# w10dc_motor.net
KiCad netlist of a schematic drawn in EAGLE
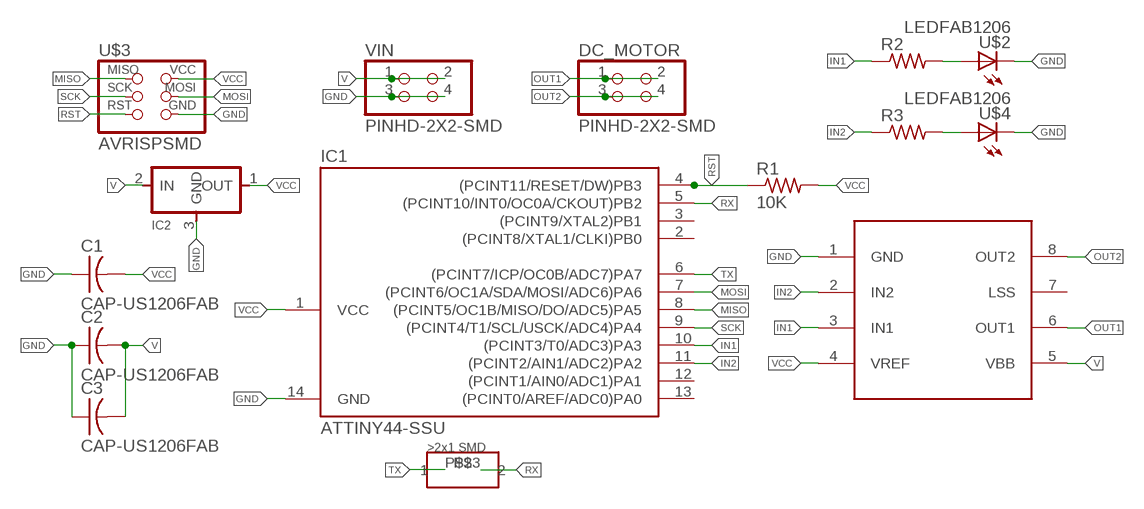
[diagram p0: schematic, sheet 1]

(export (version "E")
  (design (tool "Eeschema 10.0.6"))
  (components
    (comp (ref "C1")
      (value "CAP-US1206FAB")
      (footprint "eagle-import:C1206FAB")
      (libsource (lib "eagle-import") (part "CAP-US1206FAB"))
    )
    (comp (ref "C2")
      (value "CAP-US1206FAB")
      (footprint "eagle-import:C1206FAB")
      (libsource (lib "eagle-import") (part "CAP-US1206FAB"))
    )
    (comp (ref "C3")
      (value "CAP-US1206FAB")
      (footprint "eagle-import:C1206FAB")
      (libsource (lib "eagle-import") (part "CAP-US1206FAB"))
    )
    (comp (ref "DC_MOTOR")
      (value "PINHD-2X2-SMD")
      (footprint "eagle-import:2X02SMD")
      (libsource (lib "eagle-import") (part "PINHD-2X2-SMD"))
    )
    (comp (ref "IC1")
      (value "ATTINY44-SSU")
      (footprint "eagle-import:SOIC14")
      (libsource (lib "eagle-import") (part "ATTINY44-SSU"))
    )
    (comp (ref "IC2")
      (value "REGULATORSOT23")
      (footprint "eagle-import:SOT23")
      (libsource (lib "eagle-import") (part "REGULATORSOT23"))
    )
    (comp (ref "R1")
      (value "10K")
      (footprint "eagle-import:R1206FAB")
      (libsource (lib "eagle-import") (part "RES-US1206FAB"))
    )
    (comp (ref "R2")
      (value "RES-US1206FAB")
      (footprint "eagle-import:R1206FAB")
      (libsource (lib "eagle-import") (part "RES-US1206FAB"))
    )
    (comp (ref "R3")
      (value "RES-US1206FAB")
      (footprint "eagle-import:R1206FAB")
      (libsource (lib "eagle-import") (part "RES-US1206FAB"))
    )
    (comp (ref "U$1")
      (value "A4953-H-BRIDGE-MOTOR-DRIVER")
      (footprint "eagle-import:SOIC8")
      (libsource (lib "eagle-import") (part "A4953-H-BRIDGE-MOTOR-DRIVER"))
    )
    (comp (ref "U$2")
      (value "LEDFAB1206")
      (footprint "eagle-import:LED1206FAB")
      (libsource (lib "eagle-import") (part "LEDFAB1206"))
    )
    (comp (ref "U$3")
      (value "AVRISPSMD")
      (footprint "eagle-import:2X03SMD")
      (libsource (lib "eagle-import") (part "AVRISPSMD"))
    )
    (comp (ref "U$4")
      (value "LEDFAB1206")
      (footprint "eagle-import:LED1206FAB")
      (libsource (lib "eagle-import") (part "LEDFAB1206"))
    )
    (comp (ref "U$5")
      (value "2X1SMD")
      (footprint "eagle-import:PINHD-2X1-SMD")
      (libsource (lib "eagle-import") (part "2X1SMD"))
    )
    (comp (ref "VIN")
      (value "PINHD-2X2-SMD")
      (footprint "eagle-import:2X02SMD")
      (libsource (lib "eagle-import") (part "PINHD-2X2-SMD"))
    )
  )
  (nets
    (net (code "1") (name "GND") (class "Default")
      (node (ref "C1") (pin "1") (pinfunction "1_1") (pintype "passive"))
      (node (ref "C2") (pin "1") (pinfunction "1_1") (pintype "passive"))
      (node (ref "C3") (pin "1") (pinfunction "1_1") (pintype "passive"))
      (node (ref "IC1") (pin "14") (pinfunction "GND_14") (pintype "power_in"))
      (node (ref "IC2") (pin "3") (pinfunction "GND_3") (pintype "bidirectional"))
      (node (ref "U$1") (pin "1") (pinfunction "GND_1") (pintype "bidirectional"))
      (node (ref "U$2") (pin "2") (pinfunction "C_2") (pintype "passive"))
      (node (ref "U$3") (pin "6") (pinfunction "GND_6") (pintype "passive"))
      (node (ref "U$4") (pin "2") (pinfunction "C_2") (pintype "passive"))
      (node (ref "VIN") (pin "3") (pinfunction "3_3") (pintype "passive"))
      (node (ref "VIN") (pin "4") (pinfunction "4_4") (pintype "passive"))
    )
    (net (code "2") (name "IN1") (class "Default")
      (node (ref "IC1") (pin "10") (pinfunction "(PCINT3/T0/ADC3)PA3_10") (pintype "bidirectional"))
      (node (ref "R2") (pin "1") (pinfunction "1_1") (pintype "passive"))
      (node (ref "U$1") (pin "3") (pinfunction "IN1_3") (pintype "bidirectional"))
    )
    (net (code "3") (name "IN2") (class "Default")
      (node (ref "IC1") (pin "11") (pinfunction "(PCINT2/AIN1/ADC2)PA2_11") (pintype "bidirectional"))
      (node (ref "R3") (pin "1") (pinfunction "1_1") (pintype "passive"))
      (node (ref "U$1") (pin "2") (pinfunction "IN2_2") (pintype "bidirectional"))
    )
    (net (code "4") (name "MISO") (class "Default")
      (node (ref "IC1") (pin "8") (pinfunction "(PCINT5/OC1B/MISO/DO/ADC5)PA5_8") (pintype "bidirectional"))
      (node (ref "U$3") (pin "1") (pinfunction "MISO_1") (pintype "passive"))
    )
    (net (code "5") (name "MOSI") (class "Default")
      (node (ref "IC1") (pin "7") (pinfunction "(PCINT6/OC1A/SDA/MOSI/ADC6)PA6_7") (pintype "bidirectional"))
      (node (ref "U$3") (pin "4") (pinfunction "MOSI_4") (pintype "passive"))
    )
    (net (code "6") (name "Net-(U$2-A)") (class "Default")
      (node (ref "R2") (pin "2") (pinfunction "2_2") (pintype "passive"))
      (node (ref "U$2") (pin "1") (pinfunction "A_1") (pintype "passive"))
    )
    (net (code "7") (name "Net-(U$4-A)") (class "Default")
      (node (ref "R3") (pin "2") (pinfunction "2_2") (pintype "passive"))
      (node (ref "U$4") (pin "1") (pinfunction "A_1") (pintype "passive"))
    )
    (net (code "8") (name "OUT1") (class "Default")
      (node (ref "DC_MOTOR") (pin "1") (pinfunction "1_1") (pintype "passive"))
      (node (ref "DC_MOTOR") (pin "2") (pinfunction "2_2") (pintype "passive"))
      (node (ref "U$1") (pin "6") (pinfunction "OUT1_6") (pintype "bidirectional"))
    )
    (net (code "9") (name "OUT2") (class "Default")
      (node (ref "DC_MOTOR") (pin "3") (pinfunction "3_3") (pintype "passive"))
      (node (ref "DC_MOTOR") (pin "4") (pinfunction "4_4") (pintype "passive"))
      (node (ref "U$1") (pin "8") (pinfunction "OUT2_8") (pintype "bidirectional"))
    )
    (net (code "10") (name "RST") (class "Default")
      (node (ref "IC1") (pin "4") (pinfunction "(PCINT11/RESET/DW)PB3_4") (pintype "bidirectional"))
      (node (ref "R1") (pin "1") (pinfunction "1_1") (pintype "passive"))
      (node (ref "U$3") (pin "5") (pinfunction "RST_5") (pintype "passive"))
    )
    (net (code "11") (name "RX") (class "Default")
      (node (ref "IC1") (pin "5") (pinfunction "(PCINT10/INT0/OC0A/CKOUT)PB2_5") (pintype "bidirectional"))
      (node (ref "U$5") (pin "P$3") (pinfunction "2_P$3") (pintype "bidirectional"))
    )
    (net (code "12") (name "SCK") (class "Default")
      (node (ref "IC1") (pin "9") (pinfunction "(PCINT4/T1/SCL/USCK/ADC4)PA4_9") (pintype "bidirectional"))
      (node (ref "U$3") (pin "3") (pinfunction "SCK_3") (pintype "passive"))
    )
    (net (code "13") (name "TX") (class "Default")
      (node (ref "IC1") (pin "6") (pinfunction "(PCINT7/ICP/OC0B/ADC7)PA7_6") (pintype "bidirectional"))
      (node (ref "U$5") (pin "P$2") (pinfunction "1_P$2") (pintype "bidirectional"))
    )
    (net (code "14") (name "V") (class "Default")
      (node (ref "C2") (pin "2") (pinfunction "2_2") (pintype "passive"))
      (node (ref "C3") (pin "2") (pinfunction "2_2") (pintype "passive"))
      (node (ref "IC2") (pin "2") (pinfunction "IN_2") (pintype "bidirectional"))
      (node (ref "U$1") (pin "5") (pinfunction "VBB_5") (pintype "bidirectional"))
      (node (ref "VIN") (pin "1") (pinfunction "1_1") (pintype "passive"))
      (node (ref "VIN") (pin "2") (pinfunction "2_2") (pintype "passive"))
    )
    (net (code "15") (name "VCC") (class "Default")
      (node (ref "C1") (pin "2") (pinfunction "2_2") (pintype "passive"))
      (node (ref "IC1") (pin "1") (pinfunction "VCC_1") (pintype "power_in"))
      (node (ref "IC2") (pin "1") (pinfunction "OUT_1") (pintype "bidirectional"))
      (node (ref "R1") (pin "2") (pinfunction "2_2") (pintype "passive"))
      (node (ref "U$1") (pin "4") (pinfunction "VREF_4") (pintype "bidirectional"))
      (node (ref "U$3") (pin "2") (pinfunction "VCC_2") (pintype "passive"))
    )
    (net (code "16") (name "unconnected-(IC1-(PCINT0{slash}AREF{slash}ADC0)PA0-Pad13)") (class "Default")
      (node (ref "IC1") (pin "13") (pinfunction "(PCINT0/AREF/ADC0)PA0_13") (pintype "bidirectional"))
    )
    (net (code "17") (name "unconnected-(IC1-(PCINT1{slash}AIN0{slash}ADC1)PA1-Pad12)") (class "Default")
      (node (ref "IC1") (pin "12") (pinfunction "(PCINT1/AIN0/ADC1)PA1_12") (pintype "bidirectional"))
    )
    (net (code "18") (name "unconnected-(IC1-(PCINT8{slash}XTAL1{slash}CLKI)PB0-Pad2)") (class "Default")
      (node (ref "IC1") (pin "2") (pinfunction "(PCINT8/XTAL1/CLKI)PB0_2") (pintype "bidirectional"))
    )
    (net (code "19") (name "unconnected-(IC1-(PCINT9{slash}XTAL2)PB1-Pad3)") (class "Default")
      (node (ref "IC1") (pin "3") (pinfunction "(PCINT9/XTAL2)PB1_3") (pintype "bidirectional"))
    )
    (net (code "20") (name "unconnected-(U$1-LSS-Pad7)") (class "Default")
      (node (ref "U$1") (pin "7") (pinfunction "LSS_7") (pintype "bidirectional"))
    )
  )
)
